# Qwiic_Shield_for_Arduino.net
KiCad netlist of a schematic drawn in EAGLE
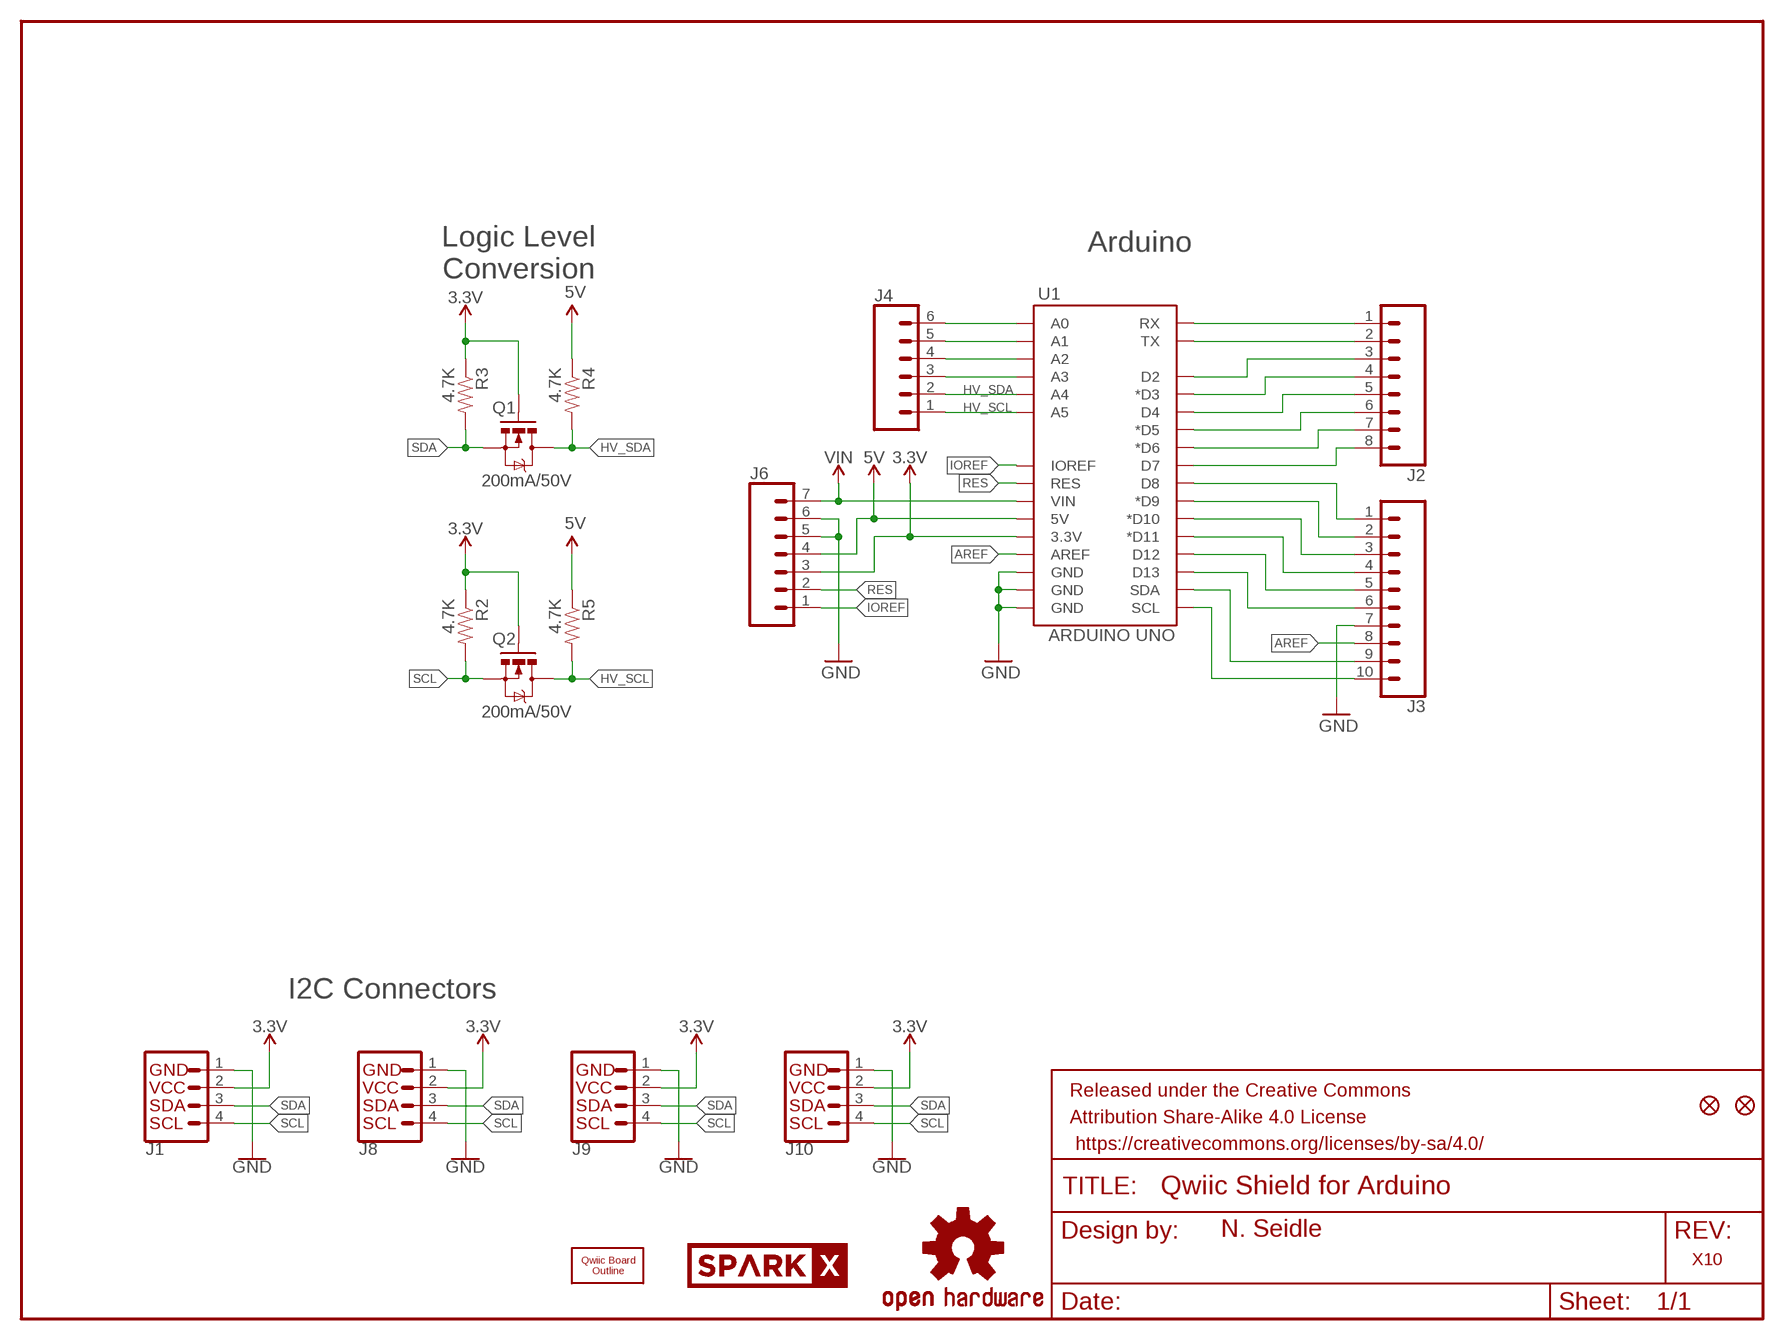
[diagram p0: schematic, sheet 1]

(export (version "E")
  (design (tool "Eeschema 10.0.6"))
  (components
    (comp (ref "FD1")
      (value "FIDUCIAL1X2")
      (footprint "eagle-import:FIDUCIAL-1X2")
      (libsource (lib "eagle-import") (part "FIDUCIAL1X2"))
    )
    (comp (ref "FD2")
      (value "FIDUCIAL1X2")
      (footprint "eagle-import:FIDUCIAL-1X2")
      (libsource (lib "eagle-import") (part "FIDUCIAL1X2"))
    )
    (comp (ref "FRAME1")
      (value "FRAME-LETTER")
      (footprint "eagle-import:CREATIVE_COMMONS")
      (libsource (lib "eagle-import") (part "FRAME-LETTER"))
    )
    (comp (ref "J1")
      (value "I2C_STANDARDJS-1MM")
      (footprint "eagle-import:1X04_1MM_RA")
      (libsource (lib "eagle-import") (part "I2C_STANDARDJS-1MM"))
    )
    (comp (ref "J2")
      (value "CONN_08NO_SILK_FEMALE_PTH")
      (footprint "eagle-import:1X08_NO_SILK")
      (libsource (lib "eagle-import") (part "CONN_08NO_SILK_FEMALE_PTH"))
    )
    (comp (ref "J3")
      (value "CONN_10NO_SILK_PTH_FEMALE")
      (footprint "eagle-import:1X10_NO_SILK")
      (libsource (lib "eagle-import") (part "CONN_10NO_SILK_PTH_FEMALE"))
    )
    (comp (ref "J4")
      (value "CONN_06NO_SILK_FEMALE_PTH")
      (footprint "eagle-import:1X06_NO_SILK")
      (libsource (lib "eagle-import") (part "CONN_06NO_SILK_FEMALE_PTH"))
    )
    (comp (ref "J6")
      (value "CONN_07NO_SILK")
      (footprint "eagle-import:1X07_NO_SILK")
      (libsource (lib "eagle-import") (part "CONN_07NO_SILK"))
    )
    (comp (ref "J8")
      (value "I2C_STANDARDJS-1MM")
      (footprint "eagle-import:1X04_1MM_RA")
      (libsource (lib "eagle-import") (part "I2C_STANDARDJS-1MM"))
    )
    (comp (ref "J9")
      (value "I2C_STANDARDJS-1MM")
      (footprint "eagle-import:1X04_1MM_RA")
      (libsource (lib "eagle-import") (part "I2C_STANDARDJS-1MM"))
    )
    (comp (ref "J10")
      (value "I2C_STANDARDJS-1MM")
      (footprint "eagle-import:1X04_1MM_RA")
      (libsource (lib "eagle-import") (part "I2C_STANDARDJS-1MM"))
    )
    (comp (ref "LOGO1")
      (value "OSHW-LOGOMINI")
      (footprint "eagle-import:OSHW-LOGO-MINI")
      (libsource (lib "eagle-import") (part "OSHW-LOGOMINI"))
    )
    (comp (ref "Q1")
      (value "200mA/50V")
      (footprint "eagle-import:SOT23-3")
      (libsource (lib "eagle-import") (part "MOSFET-NCHANNELBSS138"))
    )
    (comp (ref "Q2")
      (value "200mA/50V")
      (footprint "eagle-import:SOT23-3")
      (libsource (lib "eagle-import") (part "MOSFET-NCHANNELBSS138"))
    )
    (comp (ref "R2")
      (value "4.7K")
      (footprint "eagle-import:0603-RES")
      (libsource (lib "eagle-import") (part "4.7KOHM-1/10W-1%(0603)"))
    )
    (comp (ref "R3")
      (value "4.7K")
      (footprint "eagle-import:0603-RES")
      (libsource (lib "eagle-import") (part "4.7KOHM-1/10W-1%(0603)"))
    )
    (comp (ref "R4")
      (value "4.7K")
      (footprint "eagle-import:0603-RES")
      (libsource (lib "eagle-import") (part "4.7KOHM-1/10W-1%(0603)"))
    )
    (comp (ref "R5")
      (value "4.7K")
      (footprint "eagle-import:0603-RES")
      (libsource (lib "eagle-import") (part "4.7KOHM-1/10W-1%(0603)"))
    )
    (comp (ref "U$1")
      (value "SPARKX-LOGO3")
      (footprint "eagle-import:SPARKX-SMALL")
      (libsource (lib "eagle-import") (part "SPARKX-LOGO3"))
    )
    (comp (ref "U$2")
      (value "SPARKX-LOGO5")
      (footprint "eagle-import:SPARKX-LARGE")
      (libsource (lib "eagle-import") (part "SPARKX-LOGO5"))
    )
    (comp (ref "U$3")
      (value "QWIIC_BOARD_OUTLINEH")
      (footprint "eagle-import:QWIIC_BOARD_MOUNT_HOLES")
      (libsource (lib "eagle-import") (part "QWIIC_BOARD_OUTLINEH"))
    )
    (comp (ref "U1")
      (value "ARDUINO UNO")
      (footprint "eagle-import:UNO_R3_SHIELD_NOLABELS")
      (libsource (lib "eagle-import") (part "ARDUINO_R3_SHIELDNOLABELS"))
    )
  )
  (nets
    (net (code "1") (name "3.3V") (class "Default")
      (node (ref "J1") (pin "2") (pinfunction "VCC_2") (pintype "power_in"))
      (node (ref "J10") (pin "2") (pinfunction "VCC_2") (pintype "power_in"))
      (node (ref "J6") (pin "3") (pinfunction "3_3") (pintype "passive"))
      (node (ref "J8") (pin "2") (pinfunction "VCC_2") (pintype "power_in"))
      (node (ref "J9") (pin "2") (pinfunction "VCC_2") (pintype "power_in"))
      (node (ref "Q1") (pin "1") (pinfunction "G_1") (pintype "passive"))
      (node (ref "Q2") (pin "1") (pinfunction "G_1") (pintype "passive"))
      (node (ref "R2") (pin "1") (pinfunction "1_1") (pintype "passive"))
      (node (ref "R3") (pin "1") (pinfunction "1_1") (pintype "passive"))
      (node (ref "U1") (pin "3.3V") (pinfunction "3.3V_3.3V") (pintype "bidirectional"))
    )
    (net (code "2") (name "5V") (class "Default")
      (node (ref "J6") (pin "4") (pinfunction "4_4") (pintype "passive"))
      (node (ref "R4") (pin "1") (pinfunction "1_1") (pintype "passive"))
      (node (ref "R5") (pin "1") (pinfunction "1_1") (pintype "passive"))
      (node (ref "U1") (pin "5V") (pinfunction "5V_5V") (pintype "bidirectional"))
    )
    (net (code "3") (name "AREF") (class "Default")
      (node (ref "J3") (pin "8") (pinfunction "8_8") (pintype "passive"))
      (node (ref "U1") (pin "AREF") (pinfunction "AREF_AREF") (pintype "bidirectional"))
    )
    (net (code "4") (name "GND") (class "Default")
      (node (ref "J1") (pin "1") (pinfunction "GND_1") (pintype "power_in"))
      (node (ref "J10") (pin "1") (pinfunction "GND_1") (pintype "power_in"))
      (node (ref "J3") (pin "7") (pinfunction "7_7") (pintype "passive"))
      (node (ref "J6") (pin "5") (pinfunction "5_5") (pintype "passive"))
      (node (ref "J6") (pin "6") (pinfunction "6_6") (pintype "passive"))
      (node (ref "J8") (pin "1") (pinfunction "GND_1") (pintype "power_in"))
      (node (ref "J9") (pin "1") (pinfunction "GND_1") (pintype "power_in"))
      (node (ref "U1") (pin "GND@0") (pinfunction "GND_GND@0") (pintype "bidirectional"))
      (node (ref "U1") (pin "GND@1") (pinfunction "GND_GND@1") (pintype "bidirectional"))
      (node (ref "U1") (pin "GND@2") (pinfunction "GND_GND@2") (pintype "bidirectional"))
    )
    (net (code "5") (name "HV_SCL") (class "Default")
      (node (ref "J4") (pin "1") (pinfunction "1_1") (pintype "passive"))
      (node (ref "Q2") (pin "3") (pinfunction "D_3") (pintype "passive"))
      (node (ref "R5") (pin "2") (pinfunction "2_2") (pintype "passive"))
      (node (ref "U1") (pin "A5") (pinfunction "A5_A5") (pintype "bidirectional"))
    )
    (net (code "6") (name "HV_SDA") (class "Default")
      (node (ref "J4") (pin "2") (pinfunction "2_2") (pintype "passive"))
      (node (ref "Q1") (pin "3") (pinfunction "D_3") (pintype "passive"))
      (node (ref "R4") (pin "2") (pinfunction "2_2") (pintype "passive"))
      (node (ref "U1") (pin "A4") (pinfunction "A4_A4") (pintype "bidirectional"))
    )
    (net (code "7") (name "IOREF") (class "Default")
      (node (ref "J6") (pin "1") (pinfunction "1_1") (pintype "passive"))
      (node (ref "U1") (pin "IOREF") (pinfunction "IOREF_IOREF") (pintype "bidirectional"))
    )
    (net (code "8") (name "Net-(J2-Pad1)") (class "Default")
      (node (ref "J2") (pin "1") (pinfunction "1_1") (pintype "passive"))
      (node (ref "U1") (pin "RX") (pinfunction "RX_RX") (pintype "bidirectional"))
    )
    (net (code "9") (name "Net-(J2-Pad2)") (class "Default")
      (node (ref "J2") (pin "2") (pinfunction "2_2") (pintype "passive"))
      (node (ref "U1") (pin "TX") (pinfunction "TX_TX") (pintype "bidirectional"))
    )
    (net (code "10") (name "Net-(J2-Pad3)") (class "Default")
      (node (ref "J2") (pin "3") (pinfunction "3_3") (pintype "passive"))
      (node (ref "U1") (pin "D2") (pinfunction "D2_D2") (pintype "bidirectional"))
    )
    (net (code "11") (name "Net-(J2-Pad5)") (class "Default")
      (node (ref "J2") (pin "5") (pinfunction "5_5") (pintype "passive"))
      (node (ref "U1") (pin "D4") (pinfunction "D4_D4") (pintype "bidirectional"))
    )
    (net (code "12") (name "Net-(J2-Pad8)") (class "Default")
      (node (ref "J2") (pin "8") (pinfunction "8_8") (pintype "passive"))
      (node (ref "U1") (pin "D7") (pinfunction "D7_D7") (pintype "bidirectional"))
    )
    (net (code "13") (name "Net-(J3-Pad1)") (class "Default")
      (node (ref "J3") (pin "1") (pinfunction "1_1") (pintype "passive"))
      (node (ref "U1") (pin "D8") (pinfunction "D8_D8") (pintype "bidirectional"))
    )
    (net (code "14") (name "Net-(J3-Pad5)") (class "Default")
      (node (ref "J3") (pin "5") (pinfunction "5_5") (pintype "passive"))
      (node (ref "U1") (pin "D12") (pinfunction "D12_D12") (pintype "bidirectional"))
    )
    (net (code "15") (name "Net-(J3-Pad6)") (class "Default")
      (node (ref "J3") (pin "6") (pinfunction "6_6") (pintype "passive"))
      (node (ref "U1") (pin "D13") (pinfunction "D13_D13") (pintype "bidirectional"))
    )
    (net (code "16") (name "Net-(J3-Pad9)") (class "Default")
      (node (ref "J3") (pin "9") (pinfunction "9_9") (pintype "passive"))
      (node (ref "U1") (pin "SDA") (pinfunction "SDA_SDA") (pintype "bidirectional"))
    )
    (net (code "17") (name "Net-(J3-Pad10)") (class "Default")
      (node (ref "J3") (pin "10") (pinfunction "10_10") (pintype "passive"))
      (node (ref "U1") (pin "SCL") (pinfunction "SCL_SCL") (pintype "bidirectional"))
    )
    (net (code "18") (name "Net-(J4-Pad3)") (class "Default")
      (node (ref "J4") (pin "3") (pinfunction "3_3") (pintype "passive"))
      (node (ref "U1") (pin "A3") (pinfunction "A3_A3") (pintype "bidirectional"))
    )
    (net (code "19") (name "Net-(J4-Pad4)") (class "Default")
      (node (ref "J4") (pin "4") (pinfunction "4_4") (pintype "passive"))
      (node (ref "U1") (pin "A2") (pinfunction "A2_A2") (pintype "bidirectional"))
    )
    (net (code "20") (name "Net-(J4-Pad5)") (class "Default")
      (node (ref "J4") (pin "5") (pinfunction "5_5") (pintype "passive"))
      (node (ref "U1") (pin "A1") (pinfunction "A1_A1") (pintype "bidirectional"))
    )
    (net (code "21") (name "Net-(J4-Pad6)") (class "Default")
      (node (ref "J4") (pin "6") (pinfunction "6_6") (pintype "passive"))
      (node (ref "U1") (pin "A0") (pinfunction "A0_A0") (pintype "bidirectional"))
    )
    (net (code "22") (name "Net-(U1-*D3)") (class "Default")
      (node (ref "J2") (pin "4") (pinfunction "4_4") (pintype "passive"))
      (node (ref "U1") (pin "D3") (pinfunction "*D3_D3") (pintype "bidirectional"))
    )
    (net (code "23") (name "Net-(U1-*D5)") (class "Default")
      (node (ref "J2") (pin "6") (pinfunction "6_6") (pintype "passive"))
      (node (ref "U1") (pin "D5") (pinfunction "*D5_D5") (pintype "bidirectional"))
    )
    (net (code "24") (name "Net-(U1-*D6)") (class "Default")
      (node (ref "J2") (pin "7") (pinfunction "7_7") (pintype "passive"))
      (node (ref "U1") (pin "D6") (pinfunction "*D6_D6") (pintype "bidirectional"))
    )
    (net (code "25") (name "Net-(U1-*D9)") (class "Default")
      (node (ref "J3") (pin "2") (pinfunction "2_2") (pintype "passive"))
      (node (ref "U1") (pin "D9") (pinfunction "*D9_D9") (pintype "bidirectional"))
    )
    (net (code "26") (name "Net-(U1-*D10)") (class "Default")
      (node (ref "J3") (pin "3") (pinfunction "3_3") (pintype "passive"))
      (node (ref "U1") (pin "D10") (pinfunction "*D10_D10") (pintype "bidirectional"))
    )
    (net (code "27") (name "Net-(U1-*D11)") (class "Default")
      (node (ref "J3") (pin "4") (pinfunction "4_4") (pintype "passive"))
      (node (ref "U1") (pin "D11") (pinfunction "*D11_D11") (pintype "bidirectional"))
    )
    (net (code "28") (name "RES") (class "Default")
      (node (ref "J6") (pin "2") (pinfunction "2_2") (pintype "passive"))
      (node (ref "U1") (pin "RES") (pinfunction "RES_RES") (pintype "bidirectional"))
    )
    (net (code "29") (name "SCL") (class "Default")
      (node (ref "J1") (pin "4") (pinfunction "SCL_4") (pintype "passive"))
      (node (ref "J10") (pin "4") (pinfunction "SCL_4") (pintype "passive"))
      (node (ref "J8") (pin "4") (pinfunction "SCL_4") (pintype "passive"))
      (node (ref "J9") (pin "4") (pinfunction "SCL_4") (pintype "passive"))
      (node (ref "Q2") (pin "2") (pinfunction "S_2") (pintype "passive"))
      (node (ref "R2") (pin "2") (pinfunction "2_2") (pintype "passive"))
    )
    (net (code "30") (name "SDA") (class "Default")
      (node (ref "J1") (pin "3") (pinfunction "SDA_3") (pintype "passive"))
      (node (ref "J10") (pin "3") (pinfunction "SDA_3") (pintype "passive"))
      (node (ref "J8") (pin "3") (pinfunction "SDA_3") (pintype "passive"))
      (node (ref "J9") (pin "3") (pinfunction "SDA_3") (pintype "passive"))
      (node (ref "Q1") (pin "2") (pinfunction "S_2") (pintype "passive"))
      (node (ref "R3") (pin "2") (pinfunction "2_2") (pintype "passive"))
    )
    (net (code "31") (name "VIN") (class "Default")
      (node (ref "J6") (pin "7") (pinfunction "7_7") (pintype "passive"))
      (node (ref "U1") (pin "VIN") (pinfunction "VIN_VIN") (pintype "bidirectional"))
    )
  )
)
